# TC_board.net
KiCad netlist of a schematic drawn in EAGLE
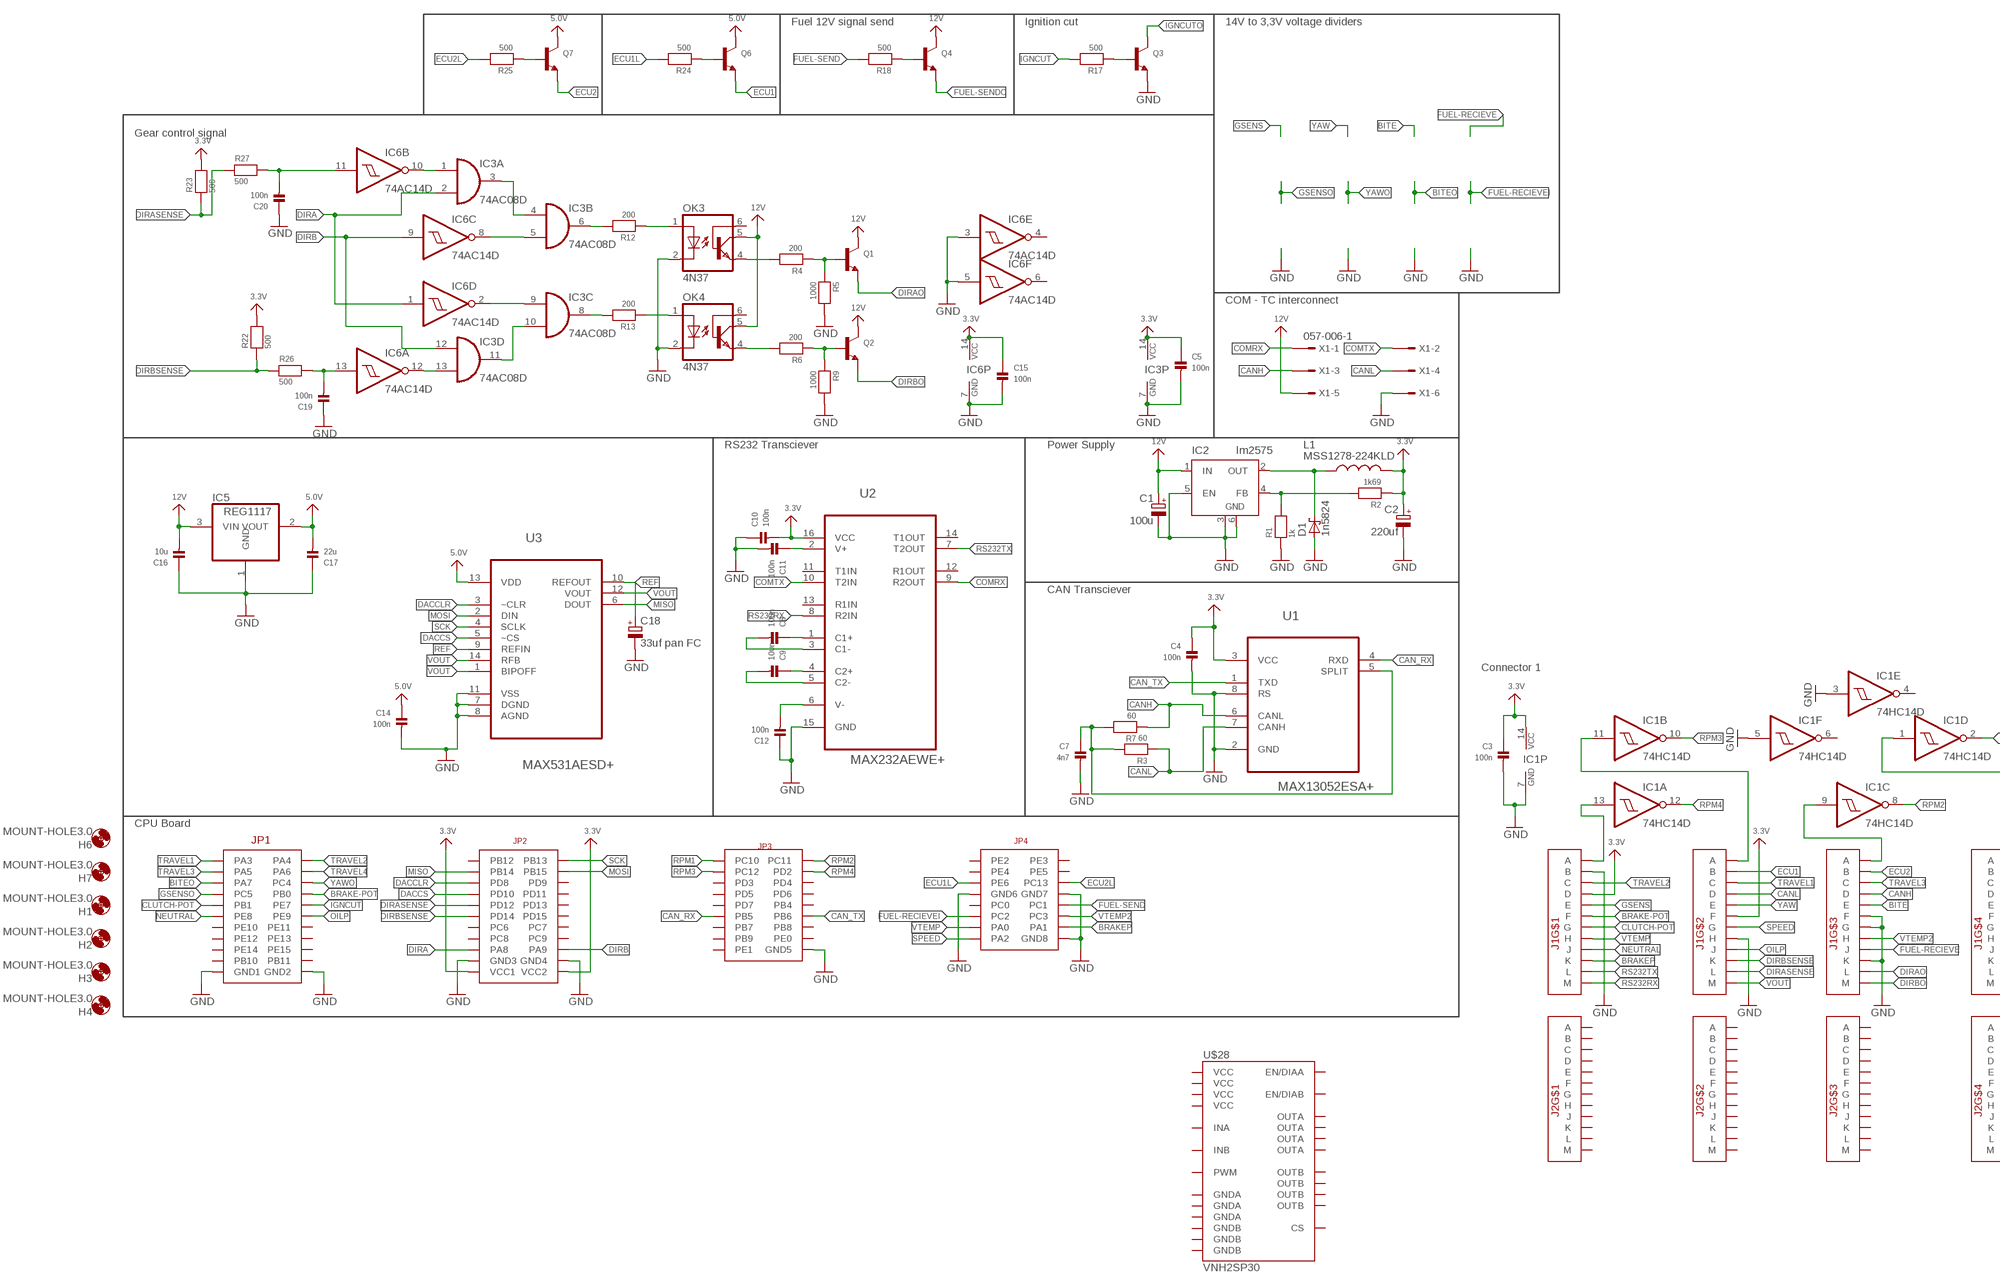
[diagram p0: schematic, sheet 1, part 1 of 2]
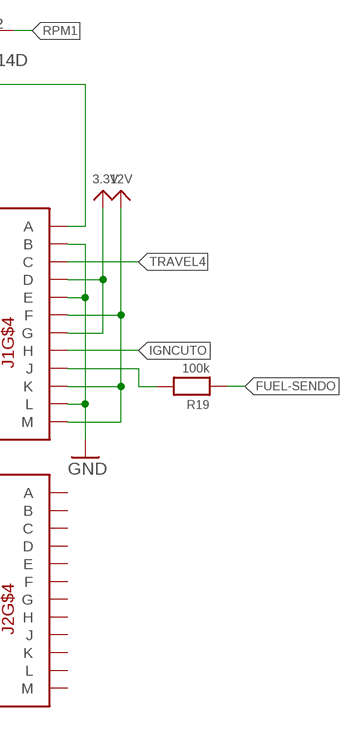
[diagram p1: schematic, sheet 1, part 2 of 2]

(export (version "E")
  (design (tool "Eeschema 10.0.6"))
  (components
    (comp (ref "C1")
      (value "100u")
      (footprint "eagle-import:E2,5-7")
      (libsource (lib "eagle-import") (part "CPOL-EUE2.5-7"))
    )
    (comp (ref "C2")
      (value "220uf")
      (footprint "eagle-import:E3,5-8")
      (libsource (lib "eagle-import") (part "CPOL-EUE3.5-8"))
    )
    (comp (ref "C3")
      (value "100n")
      (footprint "eagle-import:_0603")
      (libsource (lib "eagle-import") (part "CAP_CERAMIC_0603"))
    )
    (comp (ref "C4")
      (value "100n")
      (footprint "eagle-import:_0603")
      (libsource (lib "eagle-import") (part "CAP_CERAMIC_0603"))
    )
    (comp (ref "C5")
      (value "100n")
      (footprint "eagle-import:_0603")
      (libsource (lib "eagle-import") (part "CAP_CERAMIC_0603"))
    )
    (comp (ref "C7")
      (value "4n7")
      (footprint "eagle-import:_0603")
      (libsource (lib "eagle-import") (part "CAP_CERAMIC_0603"))
    )
    (comp (ref "C8")
      (value "100n")
      (footprint "eagle-import:_0603")
      (libsource (lib "eagle-import") (part "CAP_CERAMIC_0603"))
    )
    (comp (ref "C9")
      (value "100n")
      (footprint "eagle-import:_0603")
      (libsource (lib "eagle-import") (part "CAP_CERAMIC_0603"))
    )
    (comp (ref "C10")
      (value "100n")
      (footprint "eagle-import:_0603")
      (libsource (lib "eagle-import") (part "CAP_CERAMIC_0603"))
    )
    (comp (ref "C11")
      (value "100n")
      (footprint "eagle-import:_0603")
      (libsource (lib "eagle-import") (part "CAP_CERAMIC_0603"))
    )
    (comp (ref "C12")
      (value "100n")
      (footprint "eagle-import:_0603")
      (libsource (lib "eagle-import") (part "CAP_CERAMIC_0603"))
    )
    (comp (ref "C14")
      (value "100n")
      (footprint "eagle-import:_0603")
      (libsource (lib "eagle-import") (part "CAP_CERAMIC_0603"))
    )
    (comp (ref "C15")
      (value "100n")
      (footprint "eagle-import:_0603")
      (libsource (lib "eagle-import") (part "CAP_CERAMIC_0603"))
    )
    (comp (ref "C16")
      (value "10u")
      (footprint "eagle-import:_0805")
      (libsource (lib "eagle-import") (part "CAP_CERAMIC_0805"))
    )
    (comp (ref "C17")
      (value "22u")
      (footprint "eagle-import:_0805")
      (libsource (lib "eagle-import") (part "CAP_CERAMIC_0805"))
    )
    (comp (ref "C18")
      (value "33uf pan FC")
      (footprint "eagle-import:UD-5X5,8_NICHICON")
      (libsource (lib "eagle-import") (part "CPOL-EUUD-5X5,8"))
    )
    (comp (ref "C19")
      (value "100n")
      (footprint "eagle-import:_0805")
      (libsource (lib "eagle-import") (part "CAP_CERAMIC_0805"))
    )
    (comp (ref "C20")
      (value "100n")
      (footprint "eagle-import:_0805")
      (libsource (lib "eagle-import") (part "CAP_CERAMIC_0805"))
    )
    (comp (ref "D1")
      (value "1n5824")
      (footprint "eagle-import:F126Z12")
      (libsource (lib "eagle-import") (part "SCHOTTKY-DIODEF126Z12"))
    )
    (comp (ref "H1")
      (value "MOUNT-HOLE3.0")
      (footprint "eagle-import:3,0")
      (libsource (lib "eagle-import") (part "MOUNT-HOLE3.0"))
    )
    (comp (ref "H2")
      (value "MOUNT-HOLE3.0")
      (footprint "eagle-import:3,0")
      (libsource (lib "eagle-import") (part "MOUNT-HOLE3.0"))
    )
    (comp (ref "H3")
      (value "MOUNT-HOLE3.0")
      (footprint "eagle-import:3,0")
      (libsource (lib "eagle-import") (part "MOUNT-HOLE3.0"))
    )
    (comp (ref "H4")
      (value "MOUNT-HOLE3.0")
      (footprint "eagle-import:3,0")
      (libsource (lib "eagle-import") (part "MOUNT-HOLE3.0"))
    )
    (comp (ref "H6")
      (value "MOUNT-HOLE3.0")
      (footprint "eagle-import:3,0")
      (libsource (lib "eagle-import") (part "MOUNT-HOLE3.0"))
    )
    (comp (ref "H7")
      (value "MOUNT-HOLE3.0")
      (footprint "eagle-import:3,0")
      (libsource (lib "eagle-import") (part "MOUNT-HOLE3.0"))
    )
    (comp (ref "IC1")
      (value "74HC14D")
      (footprint "eagle-import:SO14")
      (libsource (lib "eagle-import") (part "7414DHC"))
    )
    (comp (ref "IC2")
      (value "lm2575")
      (footprint "eagle-import:TO263-5")
      (libsource (lib "eagle-import") (part "LM2596S"))
    )
    (comp (ref "IC3")
      (value "74AC08D")
      (footprint "eagle-import:SO14")
      (libsource (lib "eagle-import") (part "7408DAC"))
    )
    (comp (ref "IC5")
      (value "REG1117")
      (footprint "eagle-import:SOT223")
      (libsource (lib "eagle-import") (part "REG1117"))
    )
    (comp (ref "IC6")
      (value "74AC14D")
      (footprint "eagle-import:SO14")
      (libsource (lib "eagle-import") (part "7414DAC"))
    )
    (comp (ref "J1")
      (value "CON1")
      (footprint "eagle-import:AUTOCONNECTOR")
      (libsource (lib "eagle-import") (part "AUTOCONNECTOR"))
    )
    (comp (ref "J2")
      (value "CON1")
      (footprint "eagle-import:AUTOCONNECTOR")
      (libsource (lib "eagle-import") (part "AUTOCONNECTOR"))
    )
    (comp (ref "L1")
      (value "MSS1278-224KLD")
      (footprint "eagle-import:CDRH125")
      (libsource (lib "eagle-import") (part "INDUCTORPWR"))
    )
    (comp (ref "OK3")
      (value "4N37")
      (footprint "eagle-import:DIL06")
      (fields (field (name "MF") "FAIRCHILD SEMICONDUCTOR"))
      (libsource (lib "eagle-import") (part "4N37"))
    )
    (comp (ref "OK4")
      (value "4N37")
      (footprint "eagle-import:DIL06")
      (fields (field (name "MF") "FAIRCHILD SEMICONDUCTOR"))
      (libsource (lib "eagle-import") (part "4N37"))
    )
    (comp (ref "Q1")
      (value "TRANSISTOR_NPNWIDE")
      (footprint "eagle-import:SOT23-WIDE")
      (libsource (lib "eagle-import") (part "TRANSISTOR_NPNWIDE"))
    )
    (comp (ref "Q2")
      (value "TRANSISTOR_NPNWIDE")
      (footprint "eagle-import:SOT23-WIDE")
      (libsource (lib "eagle-import") (part "TRANSISTOR_NPNWIDE"))
    )
    (comp (ref "Q3")
      (value "TRANSISTOR_NPNWIDE")
      (footprint "eagle-import:SOT23-WIDE")
      (libsource (lib "eagle-import") (part "TRANSISTOR_NPNWIDE"))
    )
    (comp (ref "Q4")
      (value "TRANSISTOR_NPNWIDE")
      (footprint "eagle-import:SOT23-WIDE")
      (libsource (lib "eagle-import") (part "TRANSISTOR_NPNWIDE"))
    )
    (comp (ref "Q6")
      (value "TRANSISTOR_NPNWIDE")
      (footprint "eagle-import:SOT23-WIDE")
      (libsource (lib "eagle-import") (part "TRANSISTOR_NPNWIDE"))
    )
    (comp (ref "Q7")
      (value "TRANSISTOR_NPNWIDE")
      (footprint "eagle-import:SOT23-WIDE")
      (libsource (lib "eagle-import") (part "TRANSISTOR_NPNWIDE"))
    )
    (comp (ref "R1")
      (value "1k")
      (footprint "eagle-import:_0603")
      (libsource (lib "eagle-import") (part "RESISTOR_0603"))
    )
    (comp (ref "R2")
      (value "1k69")
      (footprint "eagle-import:_0603")
      (libsource (lib "eagle-import") (part "RESISTOR_0603"))
    )
    (comp (ref "R3")
      (value "60")
      (footprint "eagle-import:_0603")
      (libsource (lib "eagle-import") (part "RESISTOR_0603"))
    )
    (comp (ref "R4")
      (value "200")
      (footprint "eagle-import:_0603")
      (libsource (lib "eagle-import") (part "RESISTOR_0603"))
    )
    (comp (ref "R5")
      (value "1000")
      (footprint "eagle-import:_0603")
      (libsource (lib "eagle-import") (part "RESISTOR_0603"))
    )
    (comp (ref "R6")
      (value "200")
      (footprint "eagle-import:_0603")
      (libsource (lib "eagle-import") (part "RESISTOR_0603"))
    )
    (comp (ref "R7")
      (value "60")
      (footprint "eagle-import:_0603")
      (libsource (lib "eagle-import") (part "RESISTOR_0603"))
    )
    (comp (ref "R9")
      (value "1000")
      (footprint "eagle-import:_0603")
      (libsource (lib "eagle-import") (part "RESISTOR_0603"))
    )
    (comp (ref "R12")
      (value "200")
      (footprint "eagle-import:_0603")
      (libsource (lib "eagle-import") (part "RESISTOR_0603"))
    )
    (comp (ref "R13")
      (value "200")
      (footprint "eagle-import:_0603")
      (libsource (lib "eagle-import") (part "RESISTOR_0603"))
    )
    (comp (ref "R17")
      (value "500")
      (footprint "eagle-import:_0603")
      (libsource (lib "eagle-import") (part "RESISTOR_0603"))
    )
    (comp (ref "R18")
      (value "500")
      (footprint "eagle-import:_0603")
      (libsource (lib "eagle-import") (part "RESISTOR_0603"))
    )
    (comp (ref "R19")
      (value "100k")
      (footprint "eagle-import:_0603")
      (libsource (lib "eagle-import") (part "RESISTOR_0603"))
    )
    (comp (ref "R22")
      (value "500")
      (footprint "eagle-import:_0603")
      (libsource (lib "eagle-import") (part "RESISTOR_0603"))
    )
    (comp (ref "R23")
      (value "500")
      (footprint "eagle-import:_0603")
      (libsource (lib "eagle-import") (part "RESISTOR_0603"))
    )
    (comp (ref "R24")
      (value "500")
      (footprint "eagle-import:_0603")
      (libsource (lib "eagle-import") (part "RESISTOR_0603"))
    )
    (comp (ref "R25")
      (value "500")
      (footprint "eagle-import:_0603")
      (libsource (lib "eagle-import") (part "RESISTOR_0603"))
    )
    (comp (ref "R26")
      (value "500")
      (footprint "eagle-import:_0603")
      (libsource (lib "eagle-import") (part "RESISTOR_0603"))
    )
    (comp (ref "R27")
      (value "500")
      (footprint "eagle-import:_0603")
      (libsource (lib "eagle-import") (part "RESISTOR_0603"))
    )
    (comp (ref "U$1")
      (value "CPU-BOARD")
      (footprint "eagle-import:CPU-BOARD-JP1")
      (libsource (lib "eagle-import") (part "CPU-BOARD"))
    )
    (comp (ref "U$28")
      (value "VNH2SP30")
      (footprint "eagle-import:VNH2SP30")
      (libsource (lib "eagle-import") (part "VNH2SP30"))
    )
    (comp (ref "U1")
      (value "MAX13052ESA+")
      (footprint "eagle-import:SOIC127P600X175-8N")
      (libsource (lib "eagle-import") (part "MAX13052ESA+"))
    )
    (comp (ref "U2")
      (value "MAX232AEWE+")
      (footprint "eagle-import:SOIC127P1032X265-16N")
      (libsource (lib "eagle-import") (part "MAX232AEWE+"))
    )
    (comp (ref "U3")
      (value "MAX531AESD+")
      (footprint "eagle-import:SOIC127P600X175-14N")
      (libsource (lib "eagle-import") (part "MAX531AESD+"))
    )
    (comp (ref "X1")
      (value "057-006-1")
      (footprint "eagle-import:057-006-1")
      (libsource (lib "eagle-import") (part "057-006-1"))
    )
  )
  (nets
    (net (code "1") (name "3.3V") (class "Default")
      (node (ref "C10") (pin "2") (pinfunction "P$2_2") (pintype "passive"))
      (node (ref "C15") (pin "1") (pinfunction "P$1_1") (pintype "passive"))
      (node (ref "C2") (pin "+") (pinfunction "+_+") (pintype "passive"))
      (node (ref "C3") (pin "1") (pinfunction "P$1_1") (pintype "passive"))
      (node (ref "C4") (pin "1") (pinfunction "P$1_1") (pintype "passive"))
      (node (ref "C5") (pin "1") (pinfunction "P$1_1") (pintype "passive"))
      (node (ref "IC1") (pin "14") (pinfunction "VCC_14") (pintype "power_in"))
      (node (ref "IC3") (pin "14") (pinfunction "VCC_14") (pintype "power_in"))
      (node (ref "IC6") (pin "14") (pinfunction "VCC_14") (pintype "power_in"))
      (node (ref "J1") (pin "D1") (pinfunction "D_D1") (pintype "bidirectional"))
      (node (ref "J1") (pin "D4") (pinfunction "D_D4") (pintype "bidirectional"))
      (node (ref "J1") (pin "F2") (pinfunction "F_F2") (pintype "bidirectional"))
      (node (ref "J1") (pin "G4") (pinfunction "G_G4") (pintype "bidirectional"))
      (node (ref "L1") (pin "2") (pinfunction "2_2") (pintype "passive"))
      (node (ref "R2") (pin "1") (pinfunction "1_1") (pintype "passive"))
      (node (ref "R22") (pin "2") (pinfunction "2_2") (pintype "passive"))
      (node (ref "R23") (pin "2") (pinfunction "2_2") (pintype "passive"))
      (node (ref "U$1") (pin "P$43") (pinfunction "VCC1_P$43") (pintype "bidirectional"))
      (node (ref "U$1") (pin "P$44") (pinfunction "VCC2_P$44") (pintype "bidirectional"))
      (node (ref "U1") (pin "3") (pinfunction "VCC_3") (pintype "power_in"))
      (node (ref "U2") (pin "16") (pinfunction "VCC_16") (pintype "power_in"))
    )
    (net (code "2") (name "5.0V") (class "Default")
      (node (ref "C14") (pin "1") (pinfunction "P$1_1") (pintype "passive"))
      (node (ref "C17") (pin "2") (pinfunction "P$2_2") (pintype "passive"))
      (node (ref "IC5") (pin "2") (pinfunction "VOUT_2") (pintype "output"))
      (node (ref "Q6") (pin "3") (pinfunction "C_3") (pintype "passive"))
      (node (ref "Q7") (pin "3") (pinfunction "C_3") (pintype "passive"))
      (node (ref "U3") (pin "13") (pinfunction "VDD_13") (pintype "power_in"))
    )
    (net (code "3") (name "12V") (class "Default")
      (node (ref "C1") (pin "+") (pinfunction "+_+") (pintype "passive"))
      (node (ref "C16") (pin "2") (pinfunction "P$2_2") (pintype "passive"))
      (node (ref "IC2") (pin "1") (pinfunction "IN_1") (pintype "input"))
      (node (ref "IC5") (pin "3") (pinfunction "VIN_3") (pintype "input"))
      (node (ref "J1") (pin "F4") (pinfunction "F_F4") (pintype "bidirectional"))
      (node (ref "J1") (pin "K4") (pinfunction "K_K4") (pintype "bidirectional"))
      (node (ref "J1") (pin "M4") (pinfunction "M_M4") (pintype "bidirectional"))
      (node (ref "OK3") (pin "5") (pinfunction "COL_5") (pintype "passive"))
      (node (ref "OK4") (pin "5") (pinfunction "COL_5") (pintype "passive"))
      (node (ref "Q1") (pin "3") (pinfunction "C_3") (pintype "passive"))
      (node (ref "Q2") (pin "3") (pinfunction "C_3") (pintype "passive"))
      (node (ref "Q4") (pin "3") (pinfunction "C_3") (pintype "passive"))
      (node (ref "X1") (pin "5") (pinfunction "S_5") (pintype "passive"))
    )
    (net (code "4") (name "BITE") (class "Default")
      (node (ref "J1") (pin "E3") (pinfunction "E_E3") (pintype "bidirectional"))
    )
    (net (code "5") (name "BITEO") (class "Default")
      (node (ref "U$1") (pin "P$5") (pinfunction "PA7_P$5") (pintype "bidirectional"))
    )
    (net (code "6") (name "BRAKE-POT") (class "Default")
      (node (ref "J1") (pin "F1") (pinfunction "F_F1") (pintype "bidirectional"))
      (node (ref "U$1") (pin "P$8") (pinfunction "PB0_P$8") (pintype "bidirectional"))
    )
    (net (code "7") (name "BRAKEP") (class "Default")
      (node (ref "J1") (pin "K1") (pinfunction "K_K1") (pintype "bidirectional"))
      (node (ref "U$1") (pin "P$76") (pinfunction "PA1_P$76") (pintype "bidirectional"))
    )
    (net (code "8") (name "CANH") (class "Default")
      (node (ref "J1") (pin "D3") (pinfunction "D_D3") (pintype "bidirectional"))
      (node (ref "R7") (pin "1") (pinfunction "1_1") (pintype "passive"))
      (node (ref "U1") (pin "6") (pinfunction "CANL_6") (pintype "input"))
      (node (ref "X1") (pin "3") (pinfunction "S_3") (pintype "passive"))
    )
    (net (code "9") (name "CANL") (class "Default")
      (node (ref "J1") (pin "D2") (pinfunction "D_D2") (pintype "bidirectional"))
      (node (ref "R3") (pin "1") (pinfunction "1_1") (pintype "passive"))
      (node (ref "U1") (pin "7") (pinfunction "CANH_7") (pintype "input"))
      (node (ref "X1") (pin "4") (pinfunction "S_4") (pintype "passive"))
    )
    (net (code "10") (name "CAN_RX") (class "Default")
      (node (ref "U$1") (pin "P$55") (pinfunction "PB5_P$55") (pintype "bidirectional"))
      (node (ref "U1") (pin "4") (pinfunction "RXD_4") (pintype "output"))
    )
    (net (code "11") (name "CAN_TX") (class "Default")
      (node (ref "U$1") (pin "P$56") (pinfunction "PB6_P$56") (pintype "bidirectional"))
      (node (ref "U1") (pin "1") (pinfunction "TXD_1") (pintype "input"))
    )
    (net (code "12") (name "CLUTCH-POT") (class "Default")
      (node (ref "J1") (pin "G1") (pinfunction "G_G1") (pintype "bidirectional"))
      (node (ref "U$1") (pin "P$9") (pinfunction "PB1_P$9") (pintype "bidirectional"))
    )
    (net (code "13") (name "COMRX") (class "Default")
      (node (ref "U2") (pin "9") (pinfunction "R2OUT_9") (pintype "output"))
      (node (ref "X1") (pin "1") (pinfunction "S_1") (pintype "passive"))
    )
    (net (code "14") (name "COMTX") (class "Default")
      (node (ref "U2") (pin "10") (pinfunction "T2IN_10") (pintype "input"))
      (node (ref "X1") (pin "2") (pinfunction "S_2") (pintype "passive"))
    )
    (net (code "15") (name "DACCLR") (class "Default")
      (node (ref "U$1") (pin "P$27") (pinfunction "PD8_P$27") (pintype "bidirectional"))
      (node (ref "U3") (pin "3") (pinfunction "~{CLR}_3") (pintype "input"))
    )
    (net (code "16") (name "DACCS") (class "Default")
      (node (ref "U$1") (pin "P$29") (pinfunction "PD10_P$29") (pintype "bidirectional"))
      (node (ref "U3") (pin "5") (pinfunction "~{CS}_5") (pintype "input"))
    )
    (net (code "17") (name "DIRA") (class "Default")
      (node (ref "IC3") (pin "2") (pinfunction "I1_2") (pintype "input"))
      (node (ref "IC6") (pin "1") (pinfunction "I_1") (pintype "input"))
      (node (ref "U$1") (pin "P$39") (pinfunction "PA8_P$39") (pintype "bidirectional"))
    )
    (net (code "18") (name "DIRAO") (class "Default")
      (node (ref "J1") (pin "L3") (pinfunction "L_L3") (pintype "bidirectional"))
      (node (ref "Q1") (pin "2") (pinfunction "E_2") (pintype "passive"))
    )
    (net (code "19") (name "DIRASENSE") (class "Default")
      (node (ref "J1") (pin "L2") (pinfunction "L_L2") (pintype "bidirectional"))
      (node (ref "R23") (pin "1") (pinfunction "1_1") (pintype "passive"))
      (node (ref "R27") (pin "1") (pinfunction "1_1") (pintype "passive"))
      (node (ref "U$1") (pin "P$31") (pinfunction "PD12_P$31") (pintype "bidirectional"))
    )
    (net (code "20") (name "DIRB") (class "Default")
      (node (ref "IC3") (pin "12") (pinfunction "I0_12") (pintype "input"))
      (node (ref "IC6") (pin "9") (pinfunction "I_9") (pintype "input"))
      (node (ref "U$1") (pin "P$40") (pinfunction "PA9_P$40") (pintype "bidirectional"))
    )
    (net (code "21") (name "DIRBO") (class "Default")
      (node (ref "J1") (pin "M3") (pinfunction "M_M3") (pintype "bidirectional"))
      (node (ref "Q2") (pin "2") (pinfunction "E_2") (pintype "passive"))
    )
    (net (code "22") (name "DIRBSENSE") (class "Default")
      (node (ref "J1") (pin "K2") (pinfunction "K_K2") (pintype "bidirectional"))
      (node (ref "R22") (pin "1") (pinfunction "1_1") (pintype "passive"))
      (node (ref "R26") (pin "1") (pinfunction "1_1") (pintype "passive"))
      (node (ref "U$1") (pin "P$33") (pinfunction "PD14_P$33") (pintype "bidirectional"))
    )
    (net (code "23") (name "ECU1") (class "Default")
      (node (ref "J1") (pin "B2") (pinfunction "B_B2") (pintype "bidirectional"))
      (node (ref "Q6") (pin "2") (pinfunction "E_2") (pintype "passive"))
    )
    (net (code "24") (name "ECU1L") (class "Default")
      (node (ref "R24") (pin "2") (pinfunction "2_2") (pintype "passive"))
      (node (ref "U$1") (pin "P$67") (pinfunction "PE6_P$67") (pintype "bidirectional"))
    )
    (net (code "25") (name "ECU2") (class "Default")
      (node (ref "J1") (pin "B3") (pinfunction "B_B3") (pintype "bidirectional"))
      (node (ref "Q7") (pin "2") (pinfunction "E_2") (pintype "passive"))
    )
    (net (code "26") (name "ECU2L") (class "Default")
      (node (ref "R25") (pin "2") (pinfunction "2_2") (pintype "passive"))
      (node (ref "U$1") (pin "P$68") (pinfunction "PC13_P$68") (pintype "bidirectional"))
    )
    (net (code "27") (name "FUEL-RECIEVE") (class "Default")
      (node (ref "J1") (pin "J3") (pinfunction "J_J3") (pintype "bidirectional"))
    )
    (net (code "28") (name "FUEL-RECIEVEI") (class "Default")
      (node (ref "U$1") (pin "P$73") (pinfunction "PC2_P$73") (pintype "bidirectional"))
    )
    (net (code "29") (name "FUEL-SEND") (class "Default")
      (node (ref "R18") (pin "2") (pinfunction "2_2") (pintype "passive"))
      (node (ref "U$1") (pin "P$72") (pinfunction "PC1_P$72") (pintype "bidirectional"))
    )
    (net (code "30") (name "FUEL-SENDO") (class "Default")
      (node (ref "Q4") (pin "2") (pinfunction "E_2") (pintype "passive"))
      (node (ref "R19") (pin "1") (pinfunction "1_1") (pintype "passive"))
    )
    (net (code "31") (name "GND") (class "Default")
      (node (ref "C1") (pin "-") (pinfunction "-_-") (pintype "passive"))
      (node (ref "C10") (pin "1") (pinfunction "P$1_1") (pintype "passive"))
      (node (ref "C11") (pin "2") (pinfunction "P$2_2") (pintype "passive"))
      (node (ref "C12") (pin "1") (pinfunction "P$1_1") (pintype "passive"))
      (node (ref "C14") (pin "2") (pinfunction "P$2_2") (pintype "passive"))
      (node (ref "C15") (pin "2") (pinfunction "P$2_2") (pintype "passive"))
      (node (ref "C16") (pin "1") (pinfunction "P$1_1") (pintype "passive"))
      (node (ref "C17") (pin "1") (pinfunction "P$1_1") (pintype "passive"))
      (node (ref "C18") (pin "-") (pinfunction "-_-") (pintype "passive"))
      (node (ref "C19") (pin "1") (pinfunction "P$1_1") (pintype "passive"))
      (node (ref "C2") (pin "-") (pinfunction "-_-") (pintype "passive"))
      (node (ref "C20") (pin "1") (pinfunction "P$1_1") (pintype "passive"))
      (node (ref "C3") (pin "2") (pinfunction "P$2_2") (pintype "passive"))
      (node (ref "C4") (pin "2") (pinfunction "P$2_2") (pintype "passive"))
      (node (ref "C5") (pin "2") (pinfunction "P$2_2") (pintype "passive"))
      (node (ref "C7") (pin "2") (pinfunction "P$2_2") (pintype "passive"))
      (node (ref "D1") (pin "A") (pinfunction "A_A") (pintype "passive"))
      (node (ref "IC1") (pin "3") (pinfunction "I_3") (pintype "input"))
      (node (ref "IC1") (pin "5") (pinfunction "I_5") (pintype "input"))
      (node (ref "IC1") (pin "7") (pinfunction "GND_7") (pintype "power_in"))
      (node (ref "IC2") (pin "3") (pinfunction "GND_3") (pintype "power_in"))
      (node (ref "IC2") (pin "5") (pinfunction "EN_5") (pintype "input"))
      (node (ref "IC2") (pin "6") (pinfunction "GND_6") (pintype "power_in"))
      (node (ref "IC3") (pin "7") (pinfunction "GND_7") (pintype "power_in"))
      (node (ref "IC5") (pin "1") (pinfunction "GND_1") (pintype "power_in"))
      (node (ref "IC6") (pin "3") (pinfunction "I_3") (pintype "input"))
      (node (ref "IC6") (pin "5") (pinfunction "I_5") (pintype "input"))
      (node (ref "IC6") (pin "7") (pinfunction "GND_7") (pintype "power_in"))
      (node (ref "J1") (pin "B1") (pinfunction "B_B1") (pintype "bidirectional"))
      (node (ref "J1") (pin "B4") (pinfunction "B_B4") (pintype "bidirectional"))
      (node (ref "J1") (pin "E4") (pinfunction "E_E4") (pintype "bidirectional"))
      (node (ref "J1") (pin "F3") (pinfunction "F_F3") (pintype "bidirectional"))
      (node (ref "J1") (pin "G3") (pinfunction "G_G3") (pintype "bidirectional"))
      (node (ref "J1") (pin "H2") (pinfunction "H_H2") (pintype "bidirectional"))
      (node (ref "J1") (pin "K3") (pinfunction "K_K3") (pintype "bidirectional"))
      (node (ref "J1") (pin "L4") (pinfunction "L_L4") (pintype "bidirectional"))
      (node (ref "OK3") (pin "2") (pinfunction "C_2") (pintype "passive"))
      (node (ref "OK4") (pin "2") (pinfunction "C_2") (pintype "passive"))
      (node (ref "Q3") (pin "2") (pinfunction "E_2") (pintype "passive"))
      (node (ref "R1") (pin "1") (pinfunction "1_1") (pintype "passive"))
      (node (ref "R5") (pin "2") (pinfunction "2_2") (pintype "passive"))
      (node (ref "R9") (pin "2") (pinfunction "2_2") (pintype "passive"))
      (node (ref "U$1") (pin "P$19") (pinfunction "GND1_P$19") (pintype "bidirectional"))
      (node (ref "U$1") (pin "P$20") (pinfunction "GND2_P$20") (pintype "bidirectional"))
      (node (ref "U$1") (pin "P$41") (pinfunction "GND3_P$41") (pintype "bidirectional"))
      (node (ref "U$1") (pin "P$42") (pinfunction "GND4_P$42") (pintype "bidirectional"))
      (node (ref "U$1") (pin "P$62") (pinfunction "GND5_P$62") (pintype "bidirectional"))
      (node (ref "U$1") (pin "P$69") (pinfunction "GND6_P$69") (pintype "bidirectional"))
      (node (ref "U$1") (pin "P$70") (pinfunction "GND7_P$70") (pintype "bidirectional"))
      (node (ref "U$1") (pin "P$78") (pinfunction "GND8_P$78") (pintype "bidirectional"))
      (node (ref "U1") (pin "2") (pinfunction "GND_2") (pintype "passive"))
      (node (ref "U1") (pin "8") (pinfunction "RS_8") (pintype "input"))
      (node (ref "U2") (pin "15") (pinfunction "GND_15") (pintype "passive"))
      (node (ref "U3") (pin "11") (pinfunction "VSS_11") (pintype "power_in"))
      (node (ref "U3") (pin "7") (pinfunction "DGND_7") (pintype "passive"))
      (node (ref "U3") (pin "8") (pinfunction "AGND_8") (pintype "passive"))
      (node (ref "X1") (pin "6") (pinfunction "S_6") (pintype "passive"))
    )
    (net (code "32") (name "GSENS") (class "Default")
      (node (ref "J1") (pin "E1") (pinfunction "E_E1") (pintype "bidirectional"))
    )
    (net (code "33") (name "GSENSO") (class "Default")
      (node (ref "U$1") (pin "P$7") (pinfunction "PC5_P$7") (pintype "bidirectional"))
    )
    (net (code "34") (name "IGNCUT") (class "Default")
      (node (ref "R17") (pin "2") (pinfunction "2_2") (pintype "passive"))
      (node (ref "U$1") (pin "P$10") (pinfunction "PE7_P$10") (pintype "bidirectional"))
    )
    (net (code "35") (name "IGNCUTO") (class "Default")
      (node (ref "J1") (pin "H4") (pinfunction "H_H4") (pintype "bidirectional"))
      (node (ref "Q3") (pin "3") (pinfunction "C_3") (pintype "passive"))
    )
    (net (code "36") (name "MISO") (class "Default")
      (node (ref "U$1") (pin "P$25") (pinfunction "PB14_P$25") (pintype "bidirectional"))
      (node (ref "U3") (pin "6") (pinfunction "DOUT_6") (pintype "output"))
    )
    (net (code "37") (name "MOSI") (class "Default")
      (node (ref "U$1") (pin "P$26") (pinfunction "PB15_P$26") (pintype "bidirectional"))
      (node (ref "U3") (pin "2") (pinfunction "DIN_2") (pintype "input"))
    )
    (net (code "38") (name "NEUTRAL") (class "Default")
      (node (ref "J1") (pin "J1") (pinfunction "J_J1") (pintype "bidirectional"))
      (node (ref "U$1") (pin "P$11") (pinfunction "PE8_P$11") (pintype "bidirectional"))
    )
    (net (code "39") (name "Net-(C7-P$1)") (class "Default")
      (node (ref "C7") (pin "1") (pinfunction "P$1_1") (pintype "passive"))
      (node (ref "R3") (pin "2") (pinfunction "2_2") (pintype "passive"))
      (node (ref "R7") (pin "2") (pinfunction "2_2") (pintype "passive"))
      (node (ref "U1") (pin "5") (pinfunction "SPLIT_5") (pintype "output"))
    )
    (net (code "40") (name "Net-(C8-P$1)") (class "Default")
      (node (ref "C8") (pin "1") (pinfunction "P$1_1") (pintype "passive"))
      (node (ref "U2") (pin "1") (pinfunction "C1+_1") (pintype "input"))
    )
    (net (code "41") (name "Net-(C8-P$2)") (class "Default")
      (node (ref "C8") (pin "2") (pinfunction "P$2_2") (pintype "passive"))
      (node (ref "U2") (pin "3") (pinfunction "C1-_3") (pintype "input"))
    )
    (net (code "42") (name "Net-(C9-P$1)") (class "Default")
      (node (ref "C9") (pin "1") (pinfunction "P$1_1") (pintype "passive"))
      (node (ref "U2") (pin "4") (pinfunction "C2+_4") (pintype "input"))
    )
    (net (code "43") (name "Net-(C9-P$2)") (class "Default")
      (node (ref "C9") (pin "2") (pinfunction "P$2_2") (pintype "passive"))
      (node (ref "U2") (pin "5") (pinfunction "C2-_5") (pintype "input"))
    )
    (net (code "44") (name "Net-(C11-P$1)") (class "Default")
      (node (ref "C11") (pin "1") (pinfunction "P$1_1") (pintype "passive"))
      (node (ref "U2") (pin "2") (pinfunction "V+_2") (pintype "power_in"))
    )
    (net (code "45") (name "Net-(C12-P$2)") (class "Default")
      (node (ref "C12") (pin "2") (pinfunction "P$2_2") (pintype "passive"))
      (node (ref "U2") (pin "6") (pinfunction "V-_6") (pintype "power_in"))
    )
    (net (code "46") (name "Net-(C19-P$2)") (class "Default")
      (node (ref "C19") (pin "2") (pinfunction "P$2_2") (pintype "passive"))
      (node (ref "IC6") (pin "13") (pinfunction "I_13") (pintype "input"))
      (node (ref "R26") (pin "2") (pinfunction "2_2") (pintype "passive"))
    )
    (net (code "47") (name "Net-(C20-P$2)") (class "Default")
      (node (ref "C20") (pin "2") (pinfunction "P$2_2") (pintype "passive"))
      (node (ref "IC6") (pin "11") (pinfunction "I_11") (pintype "input"))
      (node (ref "R27") (pin "2") (pinfunction "2_2") (pintype "passive"))
    )
    (net (code "48") (name "Net-(IC1A-I)") (class "Default")
      (node (ref "IC1") (pin "13") (pinfunction "I_13") (pintype "input"))
      (node (ref "J1") (pin "A1") (pinfunction "A_A1") (pintype "bidirectional"))
    )
    (net (code "49") (name "Net-(IC1B-I)") (class "Default")
      (node (ref "IC1") (pin "11") (pinfunction "I_11") (pintype "input"))
      (node (ref "J1") (pin "A2") (pinfunction "A_A2") (pintype "bidirectional"))
    )
    (net (code "50") (name "Net-(IC1C-I)") (class "Default")
      (node (ref "IC1") (pin "9") (pinfunction "I_9") (pintype "input"))
      (node (ref "J1") (pin "A3") (pinfunction "A_A3") (pintype "bidirectional"))
    )
    (net (code "51") (name "Net-(IC1D-I)") (class "Default")
      (node (ref "IC1") (pin "1") (pinfunction "I_1") (pintype "input"))
      (node (ref "J1") (pin "A4") (pinfunction "A_A4") (pintype "bidirectional"))
    )
    (net (code "52") (name "Net-(IC2-FB)") (class "Default")
      (node (ref "IC2") (pin "4") (pinfunction "FB_4") (pintype "input"))
      (node (ref "R1") (pin "2") (pinfunction "2_2") (pintype "passive"))
      (node (ref "R2") (pin "2") (pinfunction "2_2") (pintype "passive"))
    )
    (net (code "53") (name "Net-(IC2-OUT)") (class "Default")
      (node (ref "D1") (pin "C") (pinfunction "C_C") (pintype "passive"))
      (node (ref "IC2") (pin "2") (pinfunction "OUT_2") (pintype "output"))
      (node (ref "L1") (pin "1") (pinfunction "1_1") (pintype "passive"))
    )
    (net (code "54") (name "Net-(IC3A-I0)") (class "Default")
      (node (ref "IC3") (pin "1") (pinfunction "I0_1") (pintype "input"))
      (node (ref "IC6") (pin "10") (pinfunction "O_10") (pintype "output"))
    )
    (net (code "55") (name "Net-(IC3A-O)") (class "Default")
      (node (ref "IC3") (pin "3") (pinfunction "O_3") (pintype "output"))
      (node (ref "IC3") (pin "4") (pinfunction "I0_4") (pintype "input"))
    )
    (net (code "56") (name "Net-(IC3B-I1)") (class "Default")
      (node (ref "IC3") (pin "5") (pinfunction "I1_5") (pintype "input"))
      (node (ref "IC6") (pin "8") (pinfunction "O_8") (pintype "output"))
    )
    (net (code "57") (name "Net-(IC3B-O)") (class "Default")
      (node (ref "IC3") (pin "6") (pinfunction "O_6") (pintype "output"))
      (node (ref "R12") (pin "2") (pinfunction "2_2") (pintype "passive"))
    )
    (net (code "58") (name "Net-(IC3C-I0)") (class "Default")
      (node (ref "IC3") (pin "9") (pinfunction "I0_9") (pintype "input"))
      (node (ref "IC6") (pin "2") (pinfunction "O_2") (pintype "output"))
    )
    (net (code "59") (name "Net-(IC3C-I1)") (class "Default")
      (node (ref "IC3") (pin "10") (pinfunction "I1_10") (pintype "input"))
      (node (ref "IC3") (pin "11") (pinfunction "O_11") (pintype "output"))
    )
    (net (code "60") (name "Net-(IC3C-O)") (class "Default")
      (node (ref "IC3") (pin "8") (pinfunction "O_8") (pintype "output"))
      (node (ref "R13") (pin "2") (pinfunction "2_2") (pintype "passive"))
    )
    (net (code "61") (name "Net-(IC3D-I1)") (class "Default")
      (node (ref "IC3") (pin "13") (pinfunction "I1_13") (pintype "input"))
      (node (ref "IC6") (pin "12") (pinfunction "O_12") (pintype "output"))
    )
    (net (code "62") (name "Net-(J1D-J)") (class "Default")
      (node (ref "J1") (pin "J4") (pinfunction "J_J4") (pintype "bidirectional"))
      (node (ref "R19") (pin "2") (pinfunction "2_2") (pintype "passive"))
    )
    (net (code "63") (name "Net-(OK3-A)") (class "Default")
      (node (ref "OK3") (pin "1") (pinfunction "A_1") (pintype "passive"))
      (node (ref "R12") (pin "1") (pinfunction "1_1") (pintype "passive"))
    )
    (net (code "64") (name "Net-(OK3-EMI)") (class "Default")
      (node (ref "OK3") (pin "4") (pinfunction "EMI_4") (pintype "passive"))
      (node (ref "R4") (pin "2") (pinfunction "2_2") (pintype "passive"))
    )
    (net (code "65") (name "Net-(OK4-A)") (class "Default")
      (node (ref "OK4") (pin "1") (pinfunction "A_1") (pintype "passive"))
      (node (ref "R13") (pin "1") (pinfunction "1_1") (pintype "passive"))
    )
    (net (code "66") (name "Net-(OK4-EMI)") (class "Default")
      (node (ref "OK4") (pin "4") (pinfunction "EMI_4") (pintype "passive"))
      (node (ref "R6") (pin "2") (pinfunction "2_2") (pintype "passive"))
    )
    (net (code "67") (name "Net-(Q1-B)") (class "Default")
      (node (ref "Q1") (pin "1") (pinfunction "B_1") (pintype "passive"))
      (node (ref "R4") (pin "1") (pinfunction "1_1") (pintype "passive"))
      (node (ref "R5") (pin "1") (pinfunction "1_1") (pintype "passive"))
    )
    (net (code "68") (name "Net-(Q2-B)") (class "Default")
      (node (ref "Q2") (pin "1") (pinfunction "B_1") (pintype "passive"))
      (node (ref "R6") (pin "1") (pinfunction "1_1") (pintype "passive"))
      (node (ref "R9") (pin "1") (pinfunction "1_1") (pintype "passive"))
    )
    (net (code "69") (name "Net-(Q3-B)") (class "Default")
      (node (ref "Q3") (pin "1") (pinfunction "B_1") (pintype "passive"))
      (node (ref "R17") (pin "1") (pinfunction "1_1") (pintype "passive"))
    )
    (net (code "70") (name "Net-(Q4-B)") (class "Default")
      (node (ref "Q4") (pin "1") (pinfunction "B_1") (pintype "passive"))
      (node (ref "R18") (pin "1") (pinfunction "1_1") (pintype "passive"))
    )
    (net (code "71") (name "Net-(Q6-B)") (class "Default")
      (node (ref "Q6") (pin "1") (pinfunction "B_1") (pintype "passive"))
      (node (ref "R24") (pin "1") (pinfunction "1_1") (pintype "passive"))
    )
    (net (code "72") (name "Net-(Q7-B)") (class "Default")
      (node (ref "Q7") (pin "1") (pinfunction "B_1") (pintype "passive"))
      (node (ref "R25") (pin "1") (pinfunction "1_1") (pintype "passive"))
    )
    (net (code "73") (name "OILP") (class "Default")
      (node (ref "J1") (pin "J2") (pinfunction "J_J2") (pintype "bidirectional"))
      (node (ref "U$1") (pin "P$12") (pinfunction "PE9_P$12") (pintype "bidirectional"))
    )
    (net (code "74") (name "REF") (class "Default")
      (node (ref "C18") (pin "+") (pinfunction "+_+") (pintype "passive"))
      (node (ref "U3") (pin "10") (pinfunction "REFOUT_10") (pintype "output"))
      (node (ref "U3") (pin "9") (pinfunction "REFIN_9") (pintype "input"))
    )
    (net (code "75") (name "RPM1") (class "Default")
      (node (ref "IC1") (pin "2") (pinfunction "O_2") (pintype "output"))
      (node (ref "U$1") (pin "P$45") (pinfunction "PC10_P$45") (pintype "bidirectional"))
    )
    (net (code "76") (name "RPM2") (class "Default")
      (node (ref "IC1") (pin "8") (pinfunction "O_8") (pintype "output"))
      (node (ref "U$1") (pin "P$46") (pinfunction "PC11_P$46") (pintype "bidirectional"))
    )
    (net (code "77") (name "RPM3") (class "Default")
      (node (ref "IC1") (pin "10") (pinfunction "O_10") (pintype "output"))
      (node (ref "U$1") (pin "P$47") (pinfunction "PC12_P$47") (pintype "bidirectional"))
    )
    (net (code "78") (name "RPM4") (class "Default")
      (node (ref "IC1") (pin "12") (pinfunction "O_12") (pintype "output"))
      (node (ref "U$1") (pin "P$48") (pinfunction "PD2_P$48") (pintype "bidirectional"))
    )
    (net (code "79") (name "RS232RX") (class "Default")
      (node (ref "J1") (pin "M1") (pinfunction "M_M1") (pintype "bidirectional"))
      (node (ref "U2") (pin "8") (pinfunction "R2IN_8") (pintype "input"))
    )
    (net (code "80") (name "RS232TX") (class "Default")
      (node (ref "J1") (pin "L1") (pinfunction "L_L1") (pintype "bidirectional"))
      (node (ref "U2") (pin "7") (pinfunction "T2OUT_7") (pintype "output"))
    )
    (net (code "81") (name "SCK") (class "Default")
      (node (ref "U$1") (pin "P$24") (pinfunction "PB13_P$24") (pintype "bidirectional"))
      (node (ref "U3") (pin "4") (pinfunction "SCLK_4") (pintype "input"))
    )
    (net (code "82") (name "SPEED") (class "Default")
      (node (ref "J1") (pin "G2") (pinfunction "G_G2") (pintype "bidirectional"))
      (node (ref "U$1") (pin "P$77") (pinfunction "PA2_P$77") (pintype "bidirectional"))
    )
    (net (code "83") (name "TRAVEL1") (class "Default")
      (node (ref "J1") (pin "C2") (pinfunction "C_C2") (pintype "bidirectional"))
      (node (ref "U$1") (pin "P$1") (pinfunction "PA3_P$1") (pintype "bidirectional"))
    )
    (net (code "84") (name "TRAVEL2") (class "Default")
      (node (ref "J1") (pin "C1") (pinfunction "C_C1") (pintype "bidirectional"))
      (node (ref "U$1") (pin "P$2") (pinfunction "PA4_P$2") (pintype "bidirectional"))
    )
    (net (code "85") (name "TRAVEL3") (class "Default")
      (node (ref "J1") (pin "C3") (pinfunction "C_C3") (pintype "bidirectional"))
      (node (ref "U$1") (pin "P$3") (pinfunction "PA5_P$3") (pintype "bidirectional"))
    )
    (net (code "86") (name "TRAVEL4") (class "Default")
      (node (ref "J1") (pin "C4") (pinfunction "C_C4") (pintype "bidirectional"))
      (node (ref "U$1") (pin "P$4") (pinfunction "PA6_P$4") (pintype "bidirectional"))
    )
    (net (code "87") (name "VOUT") (class "Default")
      (node (ref "J1") (pin "M2") (pinfunction "M_M2") (pintype "bidirectional"))
      (node (ref "U3") (pin "1") (pinfunction "BIPOFF_1") (pintype "passive"))
      (node (ref "U3") (pin "12") (pinfunction "VOUT_12") (pintype "output"))
      (node (ref "U3") (pin "14") (pinfunction "RFB_14") (pintype "passive"))
    )
    (net (code "88") (name "VTEMP") (class "Default")
      (node (ref "J1") (pin "H1") (pinfunction "H_H1") (pintype "bidirectional"))
      (node (ref "U$1") (pin "P$75") (pinfunction "PA0_P$75") (pintype "bidirectional"))
    )
    (net (code "89") (name "VTEMP2") (class "Default")
      (node (ref "J1") (pin "H3") (pinfunction "H_H3") (pintype "bidirectional"))
      (node (ref "U$1") (pin "P$74") (pinfunction "PC3_P$74") (pintype "bidirectional"))
    )
    (net (code "90") (name "YAW") (class "Default")
      (node (ref "J1") (pin "E2") (pinfunction "E_E2") (pintype "bidirectional"))
    )
    (net (code "91") (name "YAWO") (class "Default")
      (node (ref "U$1") (pin "P$6") (pinfunction "PC4_P$6") (pintype "bidirectional"))
    )
    (net (code "92") (name "unconnected-(IC1E-O-Pad4)") (class "Default")
      (node (ref "IC1") (pin "4") (pinfunction "O_4") (pintype "output"))
    )
    (net (code "93") (name "unconnected-(IC1F-O-Pad6)") (class "Default")
      (node (ref "IC1") (pin "6") (pinfunction "O_6") (pintype "output"))
    )
    (net (code "94") (name "unconnected-(IC6E-O-Pad4)") (class "Default")
      (node (ref "IC6") (pin "4") (pinfunction "O_4") (pintype "output"))
    )
    (net (code "95") (name "unconnected-(IC6F-O-Pad6)") (class "Default")
      (node (ref "IC6") (pin "6") (pinfunction "O_6") (pintype "output"))
    )
    (net (code "96") (name "unconnected-(J2A-A-PadA1)") (class "Default")
      (node (ref "J2") (pin "A1") (pinfunction "A_A1") (pintype "bidirectional"))
    )
    (net (code "97") (name "unconnected-(J2A-B-PadB1)") (class "Default")
      (node (ref "J2") (pin "B1") (pinfunction "B_B1") (pintype "bidirectional"))
    )
    (net (code "98") (name "unconnected-(J2A-C-PadC1)") (class "Default")
      (node (ref "J2") (pin "C1") (pinfunction "C_C1") (pintype "bidirectional"))
    )
    (net (code "99") (name "unconnected-(J2A-D-PadD1)") (class "Default")
      (node (ref "J2") (pin "D1") (pinfunction "D_D1") (pintype "bidirectional"))
    )
    (net (code "100") (name "unconnected-(J2A-E-PadE1)") (class "Default")
      (node (ref "J2") (pin "E1") (pinfunction "E_E1") (pintype "bidirectional"))
    )
    (net (code "101") (name "unconnected-(J2A-F-PadF1)") (class "Default")
      (node (ref "J2") (pin "F1") (pinfunction "F_F1") (pintype "bidirectional"))
    )
    (net (code "102") (name "unconnected-(J2A-G-PadG1)") (class "Default")
      (node (ref "J2") (pin "G1") (pinfunction "G_G1") (pintype "bidirectional"))
    )
    (net (code "103") (name "unconnected-(J2A-H-PadH1)") (class "Default")
      (node (ref "J2") (pin "H1") (pinfunction "H_H1") (pintype "bidirectional"))
    )
    (net (code "104") (name "unconnected-(J2A-J-PadJ1)") (class "Default")
      (node (ref "J2") (pin "J1") (pinfunction "J_J1") (pintype "bidirectional"))
    )
    (net (code "105") (name "unconnected-(J2A-K-PadK1)") (class "Default")
      (node (ref "J2") (pin "K1") (pinfunction "K_K1") (pintype "bidirectional"))
    )
    (net (code "106") (name "unconnected-(J2A-L-PadL1)") (class "Default")
      (node (ref "J2") (pin "L1") (pinfunction "L_L1") (pintype "bidirectional"))
    )
    (net (code "107") (name "unconnected-(J2A-M-PadM1)") (class "Default")
      (node (ref "J2") (pin "M1") (pinfunction "M_M1") (pintype "bidirectional"))
    )
    (net (code "108") (name "unconnected-(J2B-A-PadA2)") (class "Default")
      (node (ref "J2") (pin "A2") (pinfunction "A_A2") (pintype "bidirectional"))
    )
    (net (code "109") (name "unconnected-(J2B-B-PadB2)") (class "Default")
      (node (ref "J2") (pin "B2") (pinfunction "B_B2") (pintype "bidirectional"))
    )
    (net (code "110") (name "unconnected-(J2B-C-PadC2)") (class "Default")
      (node (ref "J2") (pin "C2") (pinfunction "C_C2") (pintype "bidirectional"))
    )
    (net (code "111") (name "unconnected-(J2B-D-PadD2)") (class "Default")
      (node (ref "J2") (pin "D2") (pinfunction "D_D2") (pintype "bidirectional"))
    )
    (net (code "112") (name "unconnected-(J2B-E-PadE2)") (class "Default")
      (node (ref "J2") (pin "E2") (pinfunction "E_E2") (pintype "bidirectional"))
    )
    (net (code "113") (name "unconnected-(J2B-F-PadF2)") (class "Default")
      (node (ref "J2") (pin "F2") (pinfunction "F_F2") (pintype "bidirectional"))
    )
    (net (code "114") (name "unconnected-(J2B-G-PadG2)") (class "Default")
      (node (ref "J2") (pin "G2") (pinfunction "G_G2") (pintype "bidirectional"))
    )
    (net (code "115") (name "unconnected-(J2B-H-PadH2)") (class "Default")
      (node (ref "J2") (pin "H2") (pinfunction "H_H2") (pintype "bidirectional"))
    )
    (net (code "116") (name "unconnected-(J2B-J-PadJ2)") (class "Default")
      (node (ref "J2") (pin "J2") (pinfunction "J_J2") (pintype "bidirectional"))
    )
    (net (code "117") (name "unconnected-(J2B-K-PadK2)") (class "Default")
      (node (ref "J2") (pin "K2") (pinfunction "K_K2") (pintype "bidirectional"))
    )
    (net (code "118") (name "unconnected-(J2B-L-PadL2)") (class "Default")
      (node (ref "J2") (pin "L2") (pinfunction "L_L2") (pintype "bidirectional"))
    )
    (net (code "119") (name "unconnected-(J2B-M-PadM2)") (class "Default")
      (node (ref "J2") (pin "M2") (pinfunction "M_M2") (pintype "bidirectional"))
    )
    (net (code "120") (name "unconnected-(J2C-A-PadA3)") (class "Default")
      (node (ref "J2") (pin "A3") (pinfunction "A_A3") (pintype "bidirectional"))
    )
    (net (code "121") (name "unconnected-(J2C-B-PadB3)") (class "Default")
      (node (ref "J2") (pin "B3") (pinfunction "B_B3") (pintype "bidirectional"))
    )
    (net (code "122") (name "unconnected-(J2C-C-PadC3)") (class "Default")
      (node (ref "J2") (pin "C3") (pinfunction "C_C3") (pintype "bidirectional"))
    )
    (net (code "123") (name "unconnected-(J2C-D-PadD3)") (class "Default")
      (node (ref "J2") (pin "D3") (pinfunction "D_D3") (pintype "bidirectional"))
    )
    (net (code "124") (name "unconnected-(J2C-E-PadE3)") (class "Default")
      (node (ref "J2") (pin "E3") (pinfunction "E_E3") (pintype "bidirectional"))
    )
    (net (code "125") (name "unconnected-(J2C-F-PadF3)") (class "Default")
      (node (ref "J2") (pin "F3") (pinfunction "F_F3") (pintype "bidirectional"))
    )
    (net (code "126") (name "unconnected-(J2C-G-PadG3)") (class "Default")
      (node (ref "J2") (pin "G3") (pinfunction "G_G3") (pintype "bidirectional"))
    )
    (net (code "127") (name "unconnected-(J2C-H-PadH3)") (class "Default")
      (node (ref "J2") (pin "H3") (pinfunction "H_H3") (pintype "bidirectional"))
    )
    (net (code "128") (name "unconnected-(J2C-J-PadJ3)") (class "Default")
      (node (ref "J2") (pin "J3") (pinfunction "J_J3") (pintype "bidirectional"))
    )
    (net (code "129") (name "unconnected-(J2C-K-PadK3)") (class "Default")
      (node (ref "J2") (pin "K3") (pinfunction "K_K3") (pintype "bidirectional"))
    )
    (net (code "130") (name "unconnected-(J2C-L-PadL3)") (class "Default")
      (node (ref "J2") (pin "L3") (pinfunction "L_L3") (pintype "bidirectional"))
    )
    (net (code "131") (name "unconnected-(J2C-M-PadM3)") (class "Default")
      (node (ref "J2") (pin "M3") (pinfunction "M_M3") (pintype "bidirectional"))
    )
    (net (code "132") (name "unconnected-(J2D-A-PadA4)") (class "Default")
      (node (ref "J2") (pin "A4") (pinfunction "A_A4") (pintype "bidirectional"))
    )
    (net (code "133") (name "unconnected-(J2D-B-PadB4)") (class "Default")
      (node (ref "J2") (pin "B4") (pinfunction "B_B4") (pintype "bidirectional"))
    )
    (net (code "134") (name "unconnected-(J2D-C-PadC4)") (class "Default")
      (node (ref "J2") (pin "C4") (pinfunction "C_C4") (pintype "bidirectional"))
    )
    (net (code "135") (name "unconnected-(J2D-D-PadD4)") (class "Default")
      (node (ref "J2") (pin "D4") (pinfunction "D_D4") (pintype "bidirectional"))
    )
    (net (code "136") (name "unconnected-(J2D-E-PadE4)") (class "Default")
      (node (ref "J2") (pin "E4") (pinfunction "E_E4") (pintype "bidirectional"))
    )
    (net (code "137") (name "unconnected-(J2D-F-PadF4)") (class "Default")
      (node (ref "J2") (pin "F4") (pinfunction "F_F4") (pintype "bidirectional"))
    )
    (net (code "138") (name "unconnected-(J2D-G-PadG4)") (class "Default")
      (node (ref "J2") (pin "G4") (pinfunction "G_G4") (pintype "bidirectional"))
    )
    (net (code "139") (name "unconnected-(J2D-H-PadH4)") (class "Default")
      (node (ref "J2") (pin "H4") (pinfunction "H_H4") (pintype "bidirectional"))
    )
    (net (code "140") (name "unconnected-(J2D-J-PadJ4)") (class "Default")
      (node (ref "J2") (pin "J4") (pinfunction "J_J4") (pintype "bidirectional"))
    )
    (net (code "141") (name "unconnected-(J2D-K-PadK4)") (class "Default")
      (node (ref "J2") (pin "K4") (pinfunction "K_K4") (pintype "bidirectional"))
    )
    (net (code "142") (name "unconnected-(J2D-L-PadL4)") (class "Default")
      (node (ref "J2") (pin "L4") (pinfunction "L_L4") (pintype "bidirectional"))
    )
    (net (code "143") (name "unconnected-(J2D-M-PadM4)") (class "Default")
      (node (ref "J2") (pin "M4") (pinfunction "M_M4") (pintype "bidirectional"))
    )
    (net (code "144") (name "unconnected-(OK3-BAS-Pad6)") (class "Default")
      (node (ref "OK3") (pin "6") (pinfunction "BAS_6") (pintype "passive"))
    )
    (net (code "145") (name "unconnected-(OK4-BAS-Pad6)") (class "Default")
      (node (ref "OK4") (pin "6") (pinfunction "BAS_6") (pintype "passive"))
    )
    (net (code "146") (name "unconnected-(U$1A-PB10-PadP$21)") (class "Default")
      (node (ref "U$1") (pin "P$21") (pinfunction "PB10_P$21") (pintype "bidirectional"))
    )
    (net (code "147") (name "unconnected-(U$1A-PB11-PadP$22)") (class "Default")
      (node (ref "U$1") (pin "P$22") (pinfunction "PB11_P$22") (pintype "bidirectional"))
    )
    (net (code "148") (name "unconnected-(U$1A-PE10-PadP$13)") (class "Default")
      (node (ref "U$1") (pin "P$13") (pinfunction "PE10_P$13") (pintype "bidirectional"))
    )
    (net (code "149") (name "unconnected-(U$1A-PE11-PadP$14)") (class "Default")
      (node (ref "U$1") (pin "P$14") (pinfunction "PE11_P$14") (pintype "bidirectional"))
    )
    (net (code "150") (name "unconnected-(U$1A-PE12-PadP$15)") (class "Default")
      (node (ref "U$1") (pin "P$15") (pinfunction "PE12_P$15") (pintype "bidirectional"))
    )
    (net (code "151") (name "unconnected-(U$1A-PE13-PadP$16)") (class "Default")
      (node (ref "U$1") (pin "P$16") (pinfunction "PE13_P$16") (pintype "bidirectional"))
    )
    (net (code "152") (name "unconnected-(U$1A-PE14-PadP$17)") (class "Default")
      (node (ref "U$1") (pin "P$17") (pinfunction "PE14_P$17") (pintype "bidirectional"))
    )
    (net (code "153") (name "unconnected-(U$1A-PE15-PadP$18)") (class "Default")
      (node (ref "U$1") (pin "P$18") (pinfunction "PE15_P$18") (pintype "bidirectional"))
    )
    (net (code "154") (name "unconnected-(U$1B-PB12-PadP$23)") (class "Default")
      (node (ref "U$1") (pin "P$23") (pinfunction "PB12_P$23") (pintype "bidirectional"))
    )
    (net (code "155") (name "unconnected-(U$1B-PC6-PadP$35)") (class "Default")
      (node (ref "U$1") (pin "P$35") (pinfunction "PC6_P$35") (pintype "bidirectional"))
    )
    (net (code "156") (name "unconnected-(U$1B-PC7-PadP$36)") (class "Default")
      (node (ref "U$1") (pin "P$36") (pinfunction "PC7_P$36") (pintype "bidirectional"))
    )
    (net (code "157") (name "unconnected-(U$1B-PC8-PadP$37)") (class "Default")
      (node (ref "U$1") (pin "P$37") (pinfunction "PC8_P$37") (pintype "bidirectional"))
    )
    (net (code "158") (name "unconnected-(U$1B-PC9-PadP$38)") (class "Default")
      (node (ref "U$1") (pin "P$38") (pinfunction "PC9_P$38") (pintype "bidirectional"))
    )
    (net (code "159") (name "unconnected-(U$1B-PD9-PadP$28)") (class "Default")
      (node (ref "U$1") (pin "P$28") (pinfunction "PD9_P$28") (pintype "bidirectional"))
    )
    (net (code "160") (name "unconnected-(U$1B-PD11-PadP$30)") (class "Default")
      (node (ref "U$1") (pin "P$30") (pinfunction "PD11_P$30") (pintype "bidirectional"))
    )
    (net (code "161") (name "unconnected-(U$1B-PD13-PadP$32)") (class "Default")
      (node (ref "U$1") (pin "P$32") (pinfunction "PD13_P$32") (pintype "bidirectional"))
    )
    (net (code "162") (name "unconnected-(U$1B-PD15-PadP$34)") (class "Default")
      (node (ref "U$1") (pin "P$34") (pinfunction "PD15_P$34") (pintype "bidirectional"))
    )
    (net (code "163") (name "unconnected-(U$1C-PB4-PadP$54)") (class "Default")
      (node (ref "U$1") (pin "P$54") (pinfunction "PB4_P$54") (pintype "bidirectional"))
    )
    (net (code "164") (name "unconnected-(U$1C-PB7-PadP$57)") (class "Default")
      (node (ref "U$1") (pin "P$57") (pinfunction "PB7_P$57") (pintype "bidirectional"))
    )
    (net (code "165") (name "unconnected-(U$1C-PB8-PadP$58)") (class "Default")
      (node (ref "U$1") (pin "P$58") (pinfunction "PB8_P$58") (pintype "bidirectional"))
    )
    (net (code "166") (name "unconnected-(U$1C-PB9-PadP$59)") (class "Default")
      (node (ref "U$1") (pin "P$59") (pinfunction "PB9_P$59") (pintype "bidirectional"))
    )
    (net (code "167") (name "unconnected-(U$1C-PD3-PadP$49)") (class "Default")
      (node (ref "U$1") (pin "P$49") (pinfunction "PD3_P$49") (pintype "bidirectional"))
    )
    (net (code "168") (name "unconnected-(U$1C-PD4-PadP$50)") (class "Default")
      (node (ref "U$1") (pin "P$50") (pinfunction "PD4_P$50") (pintype "bidirectional"))
    )
    (net (code "169") (name "unconnected-(U$1C-PD5-PadP$51)") (class "Default")
      (node (ref "U$1") (pin "P$51") (pinfunction "PD5_P$51") (pintype "bidirectional"))
    )
    (net (code "170") (name "unconnected-(U$1C-PD6-PadP$52)") (class "Default")
      (node (ref "U$1") (pin "P$52") (pinfunction "PD6_P$52") (pintype "bidirectional"))
    )
    (net (code "171") (name "unconnected-(U$1C-PD7-PadP$53)") (class "Default")
      (node (ref "U$1") (pin "P$53") (pinfunction "PD7_P$53") (pintype "bidirectional"))
    )
    (net (code "172") (name "unconnected-(U$1C-PE0-PadP$60)") (class "Default")
      (node (ref "U$1") (pin "P$60") (pinfunction "PE0_P$60") (pintype "bidirectional"))
    )
    (net (code "173") (name "unconnected-(U$1C-PE1-PadP$61)") (class "Default")
      (node (ref "U$1") (pin "P$61") (pinfunction "PE1_P$61") (pintype "bidirectional"))
    )
    (net (code "174") (name "unconnected-(U$1D-PC0-PadP$71)") (class "Default")
      (node (ref "U$1") (pin "P$71") (pinfunction "PC0_P$71") (pintype "bidirectional"))
    )
    (net (code "175") (name "unconnected-(U$1D-PE2-PadP$63)") (class "Default")
      (node (ref "U$1") (pin "P$63") (pinfunction "PE2_P$63") (pintype "bidirectional"))
    )
    (net (code "176") (name "unconnected-(U$1D-PE3-PadP$64)") (class "Default")
      (node (ref "U$1") (pin "P$64") (pinfunction "PE3_P$64") (pintype "bidirectional"))
    )
    (net (code "177") (name "unconnected-(U$1D-PE4-PadP$65)") (class "Default")
      (node (ref "U$1") (pin "P$65") (pinfunction "PE4_P$65") (pintype "bidirectional"))
    )
    (net (code "178") (name "unconnected-(U$1D-PE5-PadP$66)") (class "Default")
      (node (ref "U$1") (pin "P$66") (pinfunction "PE5_P$66") (pintype "bidirectional"))
    )
    (net (code "179") (name "unconnected-(U$28-CS-Pad9)") (class "Default")
      (node (ref "U$28") (pin "9") (pinfunction "CS_9") (pintype "bidirectional"))
    )
    (net (code "180") (name "unconnected-(U$28-EN{slash}DIAA-Pad6)") (class "Default")
      (node (ref "U$28") (pin "6") (pinfunction "EN/DIAA_6") (pintype "bidirectional"))
    )
    (net (code "181") (name "unconnected-(U$28-EN{slash}DIAB-Pad10)") (class "Default")
      (node (ref "U$28") (pin "10") (pinfunction "EN/DIAB_10") (pintype "bidirectional"))
    )
    (net (code "182") (name "unconnected-(U$28-GNDA-Pad26)") (class "Default")
      (node (ref "U$28") (pin "26") (pinfunction "GNDA_26") (pintype "bidirectional"))
    )
    (net (code "183") (name "unconnected-(U$28-GNDA-Pad27)") (class "Default")
      (node (ref "U$28") (pin "27") (pinfunction "GNDA_27") (pintype "bidirectional"))
    )
    (net (code "184") (name "unconnected-(U$28-GNDA-Pad28)") (class "Default")
      (node (ref "U$28") (pin "28") (pinfunction "GNDA_28") (pintype "bidirectional"))
    )
    (net (code "185") (name "unconnected-(U$28-GNDB-Pad18)") (class "Default")
      (node (ref "U$28") (pin "18") (pinfunction "GNDB_18") (pintype "bidirectional"))
    )
    (net (code "186") (name "unconnected-(U$28-GNDB-Pad19)") (class "Default")
      (node (ref "U$28") (pin "19") (pinfunction "GNDB_19") (pintype "bidirectional"))
    )
    (net (code "187") (name "unconnected-(U$28-GNDB-Pad20)") (class "Default")
      (node (ref "U$28") (pin "20") (pinfunction "GNDB_20") (pintype "bidirectional"))
    )
    (net (code "188") (name "unconnected-(U$28-INA-Pad5)") (class "Default")
      (node (ref "U$28") (pin "5") (pinfunction "INA_5") (pintype "bidirectional"))
    )
    (net (code "189") (name "unconnected-(U$28-INB-Pad11)") (class "Default")
      (node (ref "U$28") (pin "11") (pinfunction "INB_11") (pintype "bidirectional"))
    )
    (net (code "190") (name "unconnected-(U$28-OUTA-Pad1)") (class "Default")
      (node (ref "U$28") (pin "1") (pinfunction "OUTA_1") (pintype "bidirectional"))
    )
    (net (code "191") (name "unconnected-(U$28-OUTA-Pad25)") (class "Default")
      (node (ref "U$28") (pin "25") (pinfunction "OUTA_25") (pintype "bidirectional"))
    )
    (net (code "192") (name "unconnected-(U$28-OUTA-Pad30)") (class "Default")
      (node (ref "U$28") (pin "30") (pinfunction "OUTA_30") (pintype "bidirectional"))
    )
    (net (code "193") (name "unconnected-(U$28-OUTA-PadSLUG3)") (class "Default")
      (node (ref "U$28") (pin "SLUG3") (pinfunction "OUTA_SLUG3") (pintype "bidirectional"))
    )
    (net (code "194") (name "unconnected-(U$28-OUTB-Pad15)") (class "Default")
      (node (ref "U$28") (pin "15") (pinfunction "OUTB_15") (pintype "bidirectional"))
    )
    (net (code "195") (name "unconnected-(U$28-OUTB-Pad16)") (class "Default")
      (node (ref "U$28") (pin "16") (pinfunction "OUTB_16") (pintype "bidirectional"))
    )
    (net (code "196") (name "unconnected-(U$28-OUTB-Pad21)") (class "Default")
      (node (ref "U$28") (pin "21") (pinfunction "OUTB_21") (pintype "bidirectional"))
    )
    (net (code "197") (name "unconnected-(U$28-OUTB-PadSLUG2)") (class "Default")
      (node (ref "U$28") (pin "SLUG2") (pinfunction "OUTB_SLUG2") (pintype "bidirectional"))
    )
    (net (code "198") (name "unconnected-(U$28-PWM-Pad8)") (class "Default")
      (node (ref "U$28") (pin "8") (pinfunction "PWM_8") (pintype "bidirectional"))
    )
    (net (code "199") (name "unconnected-(U$28-VCC-Pad3)") (class "Default")
      (node (ref "U$28") (pin "3") (pinfunction "VCC_3") (pintype "bidirectional"))
    )
    (net (code "200") (name "unconnected-(U$28-VCC-Pad13)") (class "Default")
      (node (ref "U$28") (pin "13") (pinfunction "VCC_13") (pintype "bidirectional"))
    )
    (net (code "201") (name "unconnected-(U$28-VCC-Pad23)") (class "Default")
      (node (ref "U$28") (pin "23") (pinfunction "VCC_23") (pintype "bidirectional"))
    )
    (net (code "202") (name "unconnected-(U$28-VCC-PadSLUG1)") (class "Default")
      (node (ref "U$28") (pin "SLUG1") (pinfunction "VCC_SLUG1") (pintype "bidirectional"))
    )
    (net (code "203") (name "unconnected-(U2-R1IN-Pad13)") (class "Default")
      (node (ref "U2") (pin "13") (pinfunction "R1IN_13") (pintype "input"))
    )
    (net (code "204") (name "unconnected-(U2-R1OUT-Pad12)") (class "Default")
      (node (ref "U2") (pin "12") (pinfunction "R1OUT_12") (pintype "output"))
    )
    (net (code "205") (name "unconnected-(U2-T1IN-Pad11)") (class "Default")
      (node (ref "U2") (pin "11") (pinfunction "T1IN_11") (pintype "input"))
    )
    (net (code "206") (name "unconnected-(U2-T1OUT-Pad14)") (class "Default")
      (node (ref "U2") (pin "14") (pinfunction "T1OUT_14") (pintype "output"))
    )
  )
)
